# SCH_Linefollowerv1_2022-10-20_plan_A.net
KiCad netlist of a schematic drawn in EasyEDA
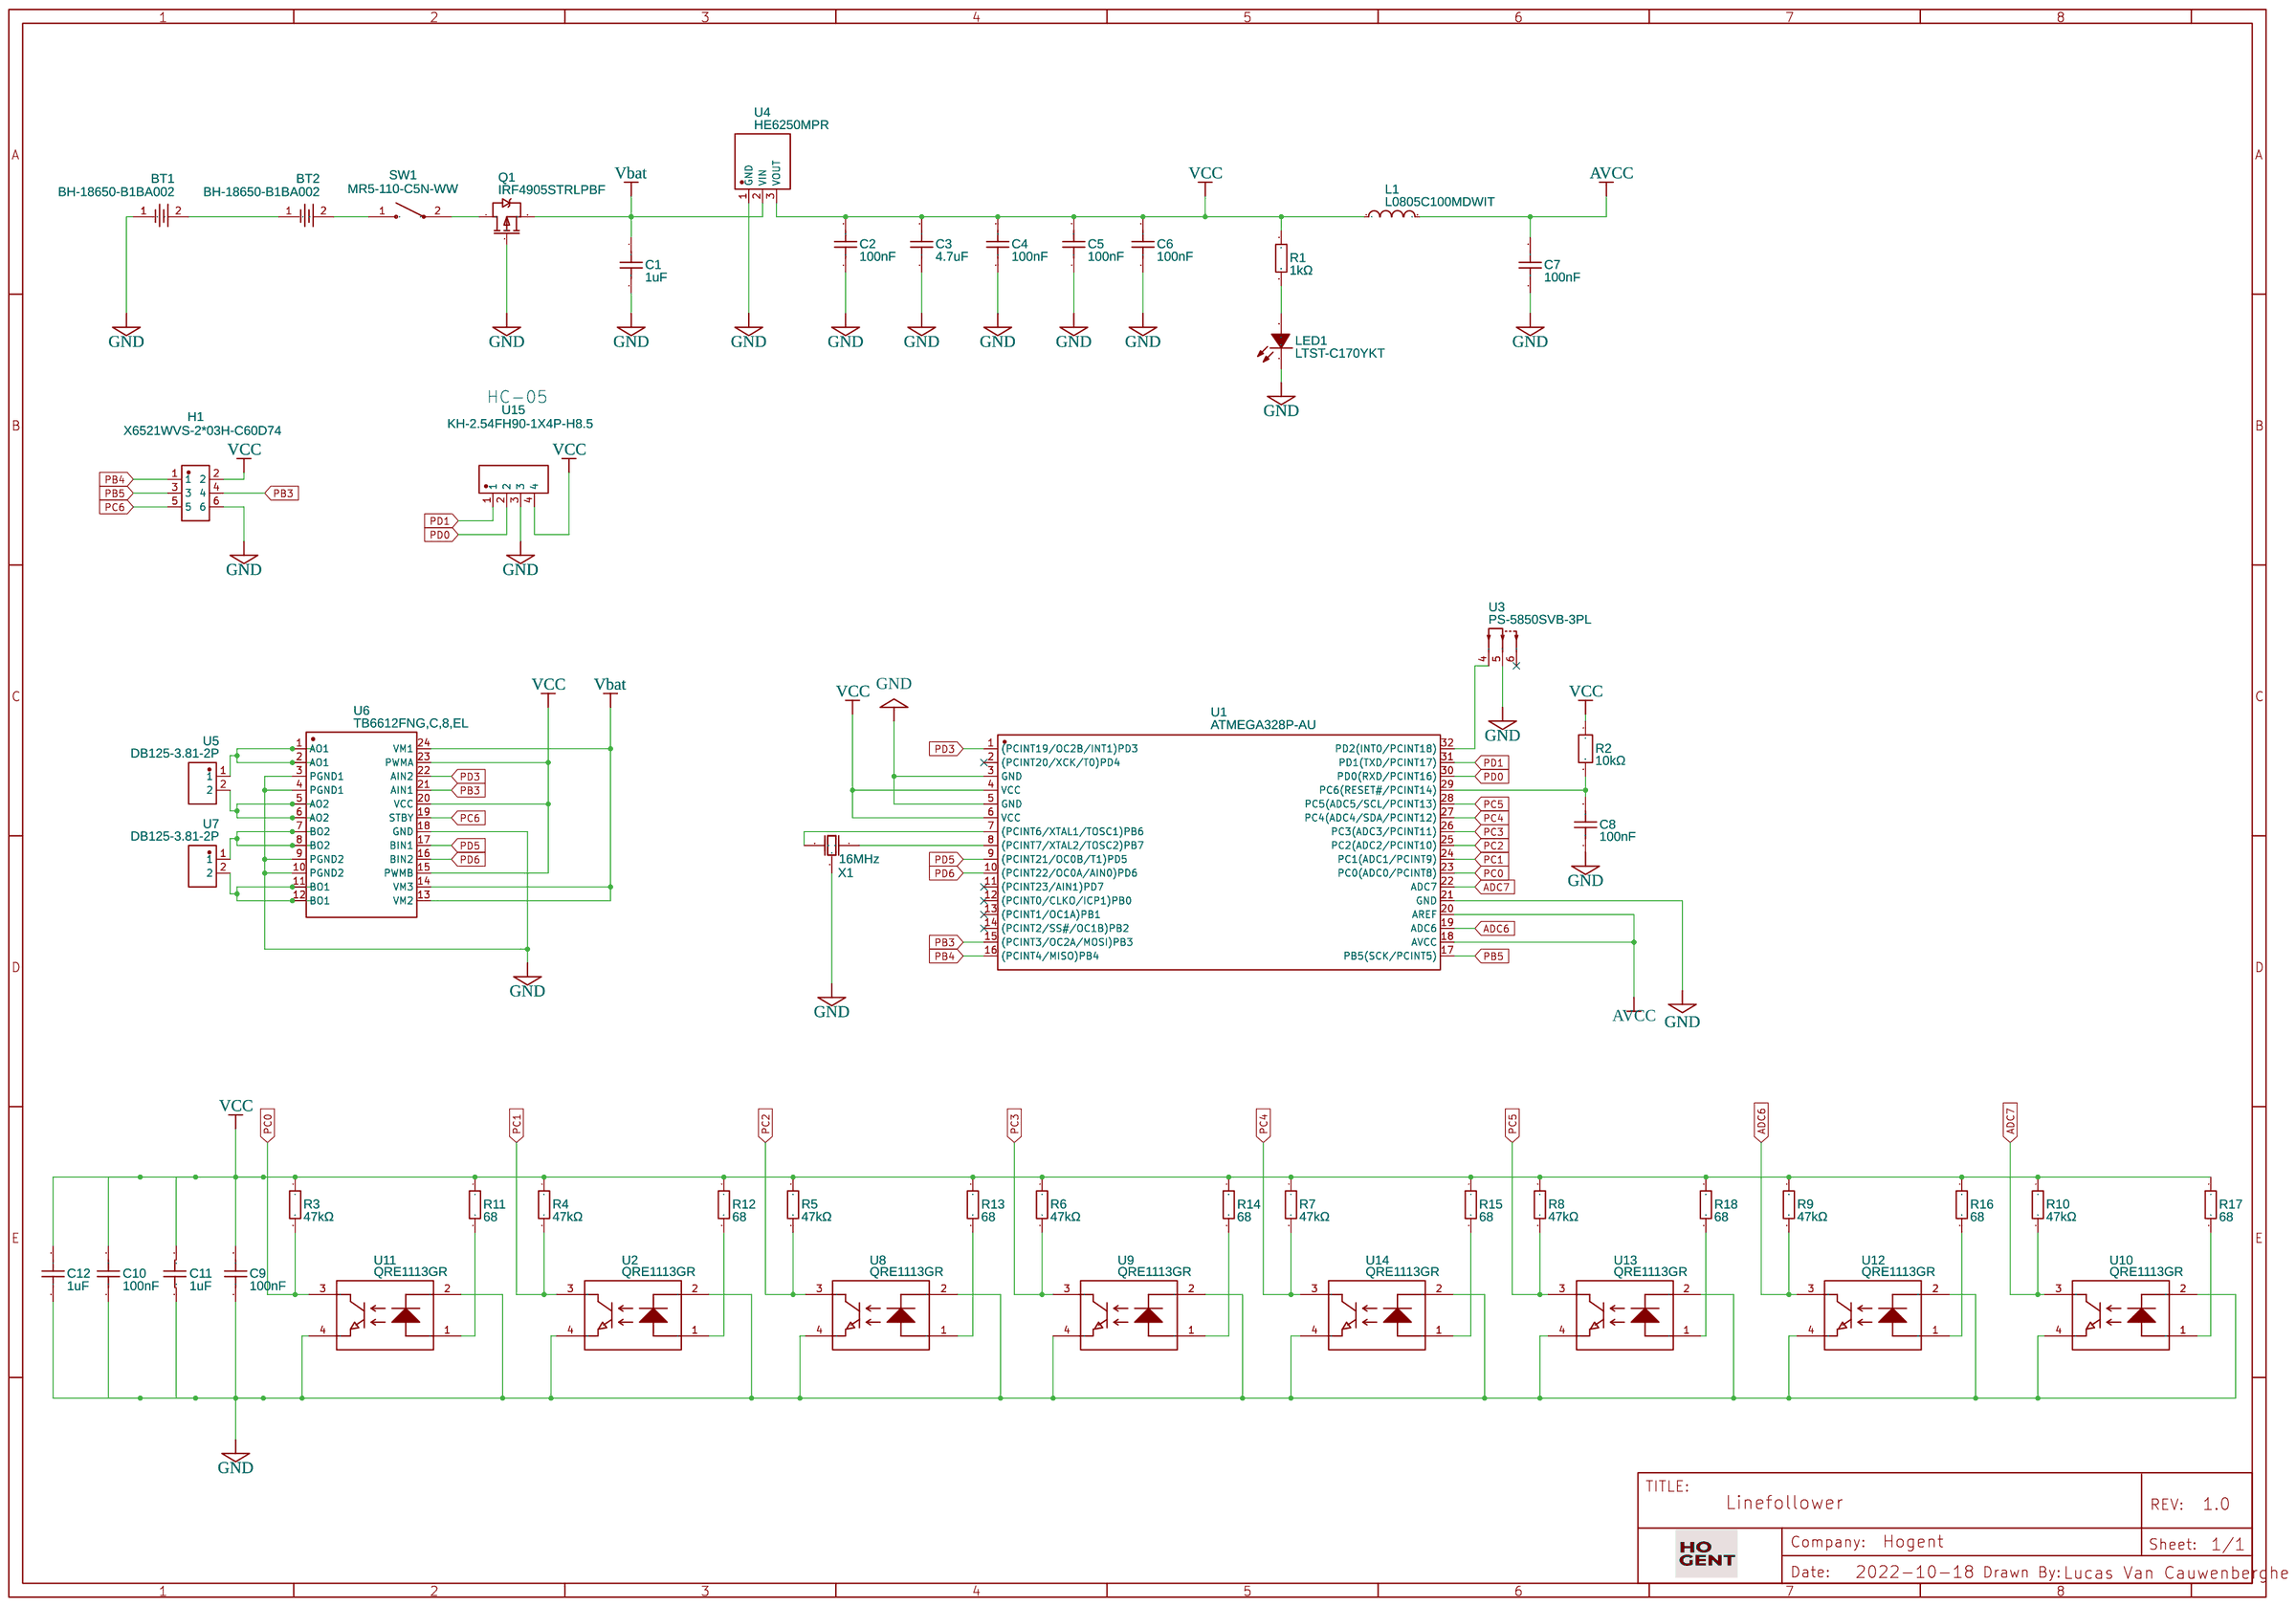
[diagram p0: schematic sheet]

(export (version "E")
  (design (tool "Eeschema 10.0.6"))
  (components
    (comp (ref "BT1")
      (value "BH-18650-B1BA002")
      (fields (field (name "BOM_Supplier Part") "C2988620"))
      (libsource (lib "") (part "BH-18650-B1BA002"))
    )
    (comp (ref "BT2")
      (value "BH-18650-B1BA002")
      (fields (field (name "BOM_Supplier Part") "C2988620"))
      (libsource (lib "") (part "BH-18650-B1BA002"))
    )
    (comp (ref "C1")
      (value "1uF")
      (fields
        (field (name "BOM_Manufacturer Part") "LMK212BJ105KD-T")
        (field (name "BOM_Supplier Part") "C92812")
      )
      (libsource (lib "") (part "LMK212BJ105KD-T"))
    )
    (comp (ref "C2")
      (value "100nF")
      (fields
        (field (name "BOM_Manufacturer Part") "LMK212SD104KG-T")
        (field (name "BOM_Supplier Part") "C386062")
      )
      (libsource (lib "") (part "LMK212SD104KG-T"))
    )
    (comp (ref "C3")
      (value "4.7uF")
      (fields
        (field (name "BOM_Manufacturer Part") "GCM21BC71A475KA73L")
        (field (name "BOM_Supplier Part") "C126583")
      )
      (libsource (lib "") (part "GCM21BC71A475KA73L"))
    )
    (comp (ref "C4")
      (value "100nF")
      (fields
        (field (name "BOM_Manufacturer Part") "LMK212SD104KG-T")
        (field (name "BOM_Supplier Part") "C386062")
      )
      (libsource (lib "") (part "LMK212SD104KG-T"))
    )
    (comp (ref "C5")
      (value "100nF")
      (fields
        (field (name "BOM_Manufacturer Part") "LMK212SD104KG-T")
        (field (name "BOM_Supplier Part") "C386062")
      )
      (libsource (lib "") (part "LMK212SD104KG-T"))
    )
    (comp (ref "C6")
      (value "100nF")
      (fields
        (field (name "BOM_Manufacturer Part") "LMK212SD104KG-T")
        (field (name "BOM_Supplier Part") "C386062")
      )
      (libsource (lib "") (part "LMK212SD104KG-T"))
    )
    (comp (ref "C7")
      (value "100nF")
      (fields
        (field (name "BOM_Manufacturer Part") "LMK212SD104KG-T")
        (field (name "BOM_Supplier Part") "C386062")
      )
      (libsource (lib "") (part "LMK212SD104KG-T"))
    )
    (comp (ref "C8")
      (value "100nF")
      (fields
        (field (name "BOM_Manufacturer Part") "LMK212SD104KG-T")
        (field (name "BOM_Supplier Part") "C386062")
      )
      (libsource (lib "") (part "LMK212SD104KG-T"))
    )
    (comp (ref "C9")
      (value "100nF")
      (fields
        (field (name "BOM_Manufacturer Part") "LMK212SD104KG-T")
        (field (name "BOM_Supplier Part") "C386062")
      )
      (libsource (lib "") (part "LMK212SD104KG-T"))
    )
    (comp (ref "C10")
      (value "100nF")
      (fields
        (field (name "BOM_Manufacturer Part") "LMK212SD104KG-T")
        (field (name "BOM_Supplier Part") "C386062")
      )
      (libsource (lib "") (part "LMK212SD104KG-T"))
    )
    (comp (ref "C11")
      (value "1uF")
      (fields
        (field (name "BOM_Manufacturer Part") "LMK212BJ105KD-T")
        (field (name "BOM_Supplier Part") "C92812")
      )
      (libsource (lib "") (part "LMK212BJ105KD-T_1"))
    )
    (comp (ref "C12")
      (value "1uF")
      (fields
        (field (name "BOM_Manufacturer Part") "LMK212BJ105KD-T")
        (field (name "BOM_Supplier Part") "C92812")
      )
      (libsource (lib "") (part "LMK212BJ105KD-T"))
    )
    (comp (ref "H1")
      (value "X6521WVS-2*03H-C60D74")
      (fields (field (name "BOM_Supplier Part") "C780054"))
      (libsource (lib "") (part "X6521WVS-2*03H-C60D74"))
    )
    (comp (ref "L1")
      (value "L0805C100MDWIT")
      (fields (field (name "BOM_Supplier Part") "C696787"))
      (libsource (lib "") (part "L0805C100MDWIT"))
    )
    (comp (ref "LED1")
      (value "LTST-C170YKT")
      (fields (field (name "BOM_Supplier Part") "C125092"))
      (libsource (lib "") (part "LTST-C170YKT"))
    )
    (comp (ref "Q1")
      (value "IRF4905STRLPBF")
      (fields (field (name "BOM_Supplier Part") "C2620"))
      (libsource (lib "") (part "IRF4905STRLPBF"))
    )
    (comp (ref "R1")
      (value "1kΩ")
      (fields
        (field (name "BOM_Manufacturer Part") "ARG05BTC1001")
        (field (name "BOM_Supplier Part") "C309081")
      )
      (libsource (lib "") (part "ARG05BTC1001"))
    )
    (comp (ref "R2")
      (value "10kΩ")
      (fields
        (field (name "BOM_Manufacturer Part") "ARG05BTC1002")
        (field (name "BOM_Supplier Part") "C406725")
      )
      (libsource (lib "") (part "ARG05BTC1002"))
    )
    (comp (ref "R3")
      (value "47kΩ")
      (fields
        (field (name "BOM_Manufacturer Part") "AECR0805F47K0K9")
        (field (name "BOM_Supplier Part") "C328397")
      )
      (libsource (lib "") (part "AECR0805F47K0K9"))
    )
    (comp (ref "R4")
      (value "47kΩ")
      (fields
        (field (name "BOM_Manufacturer Part") "AECR0805F47K0K9")
        (field (name "BOM_Supplier Part") "C328397")
      )
      (libsource (lib "") (part "AECR0805F47K0K9"))
    )
    (comp (ref "R5")
      (value "47kΩ")
      (fields
        (field (name "BOM_Manufacturer Part") "AECR0805F47K0K9")
        (field (name "BOM_Supplier Part") "C328397")
      )
      (libsource (lib "") (part "AECR0805F47K0K9"))
    )
    (comp (ref "R6")
      (value "47kΩ")
      (fields
        (field (name "BOM_Manufacturer Part") "AECR0805F47K0K9")
        (field (name "BOM_Supplier Part") "C328397")
      )
      (libsource (lib "") (part "AECR0805F47K0K9"))
    )
    (comp (ref "R7")
      (value "47kΩ")
      (fields
        (field (name "BOM_Manufacturer Part") "AECR0805F47K0K9")
        (field (name "BOM_Supplier Part") "C328397")
      )
      (libsource (lib "") (part "AECR0805F47K0K9"))
    )
    (comp (ref "R8")
      (value "47kΩ")
      (fields
        (field (name "BOM_Manufacturer Part") "AECR0805F47K0K9")
        (field (name "BOM_Supplier Part") "C328397")
      )
      (libsource (lib "") (part "AECR0805F47K0K9"))
    )
    (comp (ref "R9")
      (value "47kΩ")
      (fields
        (field (name "BOM_Manufacturer Part") "AECR0805F47K0K9")
        (field (name "BOM_Supplier Part") "C328397")
      )
      (libsource (lib "") (part "AECR0805F47K0K9"))
    )
    (comp (ref "R10")
      (value "47kΩ")
      (fields
        (field (name "BOM_Manufacturer Part") "AECR0805F47K0K9")
        (field (name "BOM_Supplier Part") "C328397")
      )
      (libsource (lib "") (part "AECR0805F47K0K9"))
    )
    (comp (ref "R11")
      (value "68")
      (fields
        (field (name "BOM_Manufacturer Part") "RC0805FR-0768RL")
        (field (name "BOM_Supplier Part") "C137498")
      )
      (libsource (lib "") (part "RC0805FR-0768RL"))
    )
    (comp (ref "R12")
      (value "68")
      (fields
        (field (name "BOM_Manufacturer Part") "RC0805FR-0768RL")
        (field (name "BOM_Supplier Part") "C137498")
      )
      (libsource (lib "") (part "RC0805FR-0768RL"))
    )
    (comp (ref "R13")
      (value "68")
      (fields
        (field (name "BOM_Manufacturer Part") "RC0805FR-0768RL")
        (field (name "BOM_Supplier Part") "C137498")
      )
      (libsource (lib "") (part "RC0805FR-0768RL"))
    )
    (comp (ref "R14")
      (value "68")
      (fields
        (field (name "BOM_Manufacturer Part") "RC0805FR-0768RL")
        (field (name "BOM_Supplier Part") "C137498")
      )
      (libsource (lib "") (part "RC0805FR-0768RL"))
    )
    (comp (ref "R15")
      (value "68")
      (fields
        (field (name "BOM_Manufacturer Part") "RC0805FR-0768RL")
        (field (name "BOM_Supplier Part") "C137498")
      )
      (libsource (lib "") (part "RC0805FR-0768RL"))
    )
    (comp (ref "R16")
      (value "68")
      (fields
        (field (name "BOM_Manufacturer Part") "RC0805FR-0768RL")
        (field (name "BOM_Supplier Part") "C137498")
      )
      (libsource (lib "") (part "RC0805FR-0768RL"))
    )
    (comp (ref "R17")
      (value "68")
      (fields
        (field (name "BOM_Manufacturer Part") "RC0805FR-0768RL")
        (field (name "BOM_Supplier Part") "C137498")
      )
      (libsource (lib "") (part "RC0805FR-0768RL"))
    )
    (comp (ref "R18")
      (value "68")
      (fields
        (field (name "BOM_Manufacturer Part") "RC0805FR-0768RL")
        (field (name "BOM_Supplier Part") "C137498")
      )
      (libsource (lib "") (part "RC0805FR-0768RL"))
    )
    (comp (ref "SW1")
      (value "MR5-110-C5N-WW")
      (fields (field (name "BOM_Supplier Part") "C2829507"))
      (libsource (lib "") (part "MR5-110-C5N-WW"))
    )
    (comp (ref "U1")
      (value "ATMEGA328P-AU")
      (fields (field (name "BOM_Supplier Part") "C14877"))
      (libsource (lib "") (part "ATMEGA328P-AU"))
    )
    (comp (ref "U2")
      (value "QRE1113GR")
      (fields (field (name "BOM_Supplier Part") "C232862"))
      (libsource (lib "") (part "QRE1113GR_5"))
    )
    (comp (ref "U3")
      (value "PS-5850SVB-3PL")
      (fields (field (name "BOM_Supplier Part") "C5159077"))
      (libsource (lib "") (part "PS-5850SVB-3PL"))
    )
    (comp (ref "U4")
      (value "HE6250MPR")
      (fields (field (name "BOM_Supplier Part") "C711940"))
      (libsource (lib "") (part "HE6250MPR"))
    )
    (comp (ref "U5")
      (value "DB125-3.81-2P")
      (fields (field (name "BOM_Supplier Part") "C395878"))
      (libsource (lib "") (part "DB125-3.81-2P"))
    )
    (comp (ref "U6")
      (value "TB6612FNG,C,8,EL")
      (fields (field (name "BOM_Supplier Part") "C141517"))
      (libsource (lib "") (part "Unknown_500_-570"))
    )
    (comp (ref "U7")
      (value "DB125-3.81-2P")
      (fields (field (name "BOM_Supplier Part") "C395878"))
      (libsource (lib "") (part "DB125-3.81-2P"))
    )
    (comp (ref "U8")
      (value "QRE1113GR")
      (fields (field (name "BOM_Supplier Part") "C232862"))
      (libsource (lib "") (part "QRE1113GR_4"))
    )
    (comp (ref "U9")
      (value "QRE1113GR")
      (fields (field (name "BOM_Supplier Part") "C232862"))
      (libsource (lib "") (part "QRE1113GR_6"))
    )
    (comp (ref "U10")
      (value "QRE1113GR")
      (fields (field (name "BOM_Supplier Part") "C232862"))
      (libsource (lib "") (part "QRE1113GR_2"))
    )
    (comp (ref "U11")
      (value "QRE1113GR")
      (fields (field (name "BOM_Supplier Part") "C232862"))
      (libsource (lib "") (part "QRE1113GR_2"))
    )
    (comp (ref "U12")
      (value "QRE1113GR")
      (fields (field (name "BOM_Supplier Part") "C232862"))
      (libsource (lib "") (part "QRE1113GR"))
    )
    (comp (ref "U13")
      (value "QRE1113GR")
      (fields (field (name "BOM_Supplier Part") "C232862"))
      (libsource (lib "") (part "QRE1113GR_3"))
    )
    (comp (ref "U14")
      (value "QRE1113GR")
      (fields (field (name "BOM_Supplier Part") "C232862"))
      (libsource (lib "") (part "QRE1113GR_1"))
    )
    (comp (ref "U15")
      (value "KH-2.54FH90-1X4P-H8.5")
      (fields (field (name "BOM_Supplier Part") "C2932680"))
      (libsource (lib "") (part "KH-2.54FH90-1X4P-H8.5"))
    )
    (comp (ref "X1")
      (value "16MHz")
      (fields
        (field (name "BOM_Manufacturer Part") "CSTNE16M0V53C000R0")
        (field (name "BOM_Supplier Part") "C882606")
      )
      (libsource (lib "") (part "CSTNE16M0V53C000R0"))
    )
  )
  (nets
    (net (code "1") (name "ADC6") (class "Default")
      (node (ref "R9") (pin "2") (pinfunction "2_2") (pintype "unspecified"))
      (node (ref "U1") (pin "19") (pinfunction "ADC6_19") (pintype "unspecified"))
      (node (ref "U12") (pin "3") (pinfunction "3_3") (pintype "input"))
    )
    (net (code "2") (name "ADC7") (class "Default")
      (node (ref "R10") (pin "2") (pinfunction "2_2") (pintype "unspecified"))
      (node (ref "U1") (pin "22") (pinfunction "ADC7_22") (pintype "unspecified"))
      (node (ref "U10") (pin "3") (pinfunction "3_3") (pintype "input"))
    )
    (net (code "3") (name "AVCC") (class "Default")
      (node (ref "C7") (pin "2") (pinfunction "2_2") (pintype "unspecified"))
      (node (ref "L1") (pin "2") (pinfunction "2_2") (pintype "unspecified"))
      (node (ref "U1") (pin "18") (pinfunction "AVCC_18") (pintype "unspecified"))
      (node (ref "U1") (pin "20") (pinfunction "AREF_20") (pintype "unspecified"))
    )
    (net (code "4") (name "GND") (class "Default")
      (node (ref "BT1") (pin "1") (pinfunction "1_1") (pintype "input"))
      (node (ref "C1") (pin "2") (pinfunction "2_2") (pintype "unspecified"))
      (node (ref "C10") (pin "1") (pinfunction "1_1") (pintype "unspecified"))
      (node (ref "C11") (pin "2") (pinfunction "2_2") (pintype "unspecified"))
      (node (ref "C12") (pin "2") (pinfunction "2_2") (pintype "unspecified"))
      (node (ref "C2") (pin "1") (pinfunction "1_1") (pintype "unspecified"))
      (node (ref "C3") (pin "1") (pinfunction "1_1") (pintype "unspecified"))
      (node (ref "C4") (pin "1") (pinfunction "1_1") (pintype "unspecified"))
      (node (ref "C5") (pin "1") (pinfunction "1_1") (pintype "unspecified"))
      (node (ref "C6") (pin "1") (pinfunction "1_1") (pintype "unspecified"))
      (node (ref "C7") (pin "1") (pinfunction "1_1") (pintype "unspecified"))
      (node (ref "C8") (pin "1") (pinfunction "1_1") (pintype "unspecified"))
      (node (ref "C9") (pin "1") (pinfunction "1_1") (pintype "unspecified"))
      (node (ref "H1") (pin "6") (pinfunction "6_6") (pintype "unspecified"))
      (node (ref "LED1") (pin "1") (pinfunction "1_1") (pintype "unspecified"))
      (node (ref "Q1") (pin "1") (pinfunction "G_1") (pintype "unspecified"))
      (node (ref "U1") (pin "21") (pinfunction "GND_21") (pintype "unspecified"))
      (node (ref "U1") (pin "3") (pinfunction "GND_3") (pintype "unspecified"))
      (node (ref "U1") (pin "5") (pinfunction "GND_5") (pintype "unspecified"))
      (node (ref "U10") (pin "2") (pinfunction "2_2") (pintype "input"))
      (node (ref "U10") (pin "4") (pinfunction "4_4") (pintype "input"))
      (node (ref "U11") (pin "2") (pinfunction "2_2") (pintype "input"))
      (node (ref "U11") (pin "4") (pinfunction "4_4") (pintype "input"))
      (node (ref "U12") (pin "2") (pinfunction "2_2") (pintype "input"))
      (node (ref "U12") (pin "4") (pinfunction "4_4") (pintype "input"))
      (node (ref "U13") (pin "2") (pinfunction "2_2") (pintype "input"))
      (node (ref "U13") (pin "4") (pinfunction "4_4") (pintype "input"))
      (node (ref "U14") (pin "2") (pinfunction "2_2") (pintype "input"))
      (node (ref "U14") (pin "4") (pinfunction "4_4") (pintype "input"))
      (node (ref "U15") (pin "3") (pinfunction "3_3") (pintype "unspecified"))
      (node (ref "U2") (pin "2") (pinfunction "2_2") (pintype "input"))
      (node (ref "U2") (pin "4") (pinfunction "4_4") (pintype "input"))
      (node (ref "U3") (pin "5") (pinfunction "5_5") (pintype "unspecified"))
      (node (ref "U4") (pin "1") (pinfunction "GND_1") (pintype "unspecified"))
      (node (ref "U6") (pin "10") (pinfunction "PGND2_10") (pintype "unspecified"))
      (node (ref "U6") (pin "18") (pinfunction "GND_18") (pintype "unspecified"))
      (node (ref "U6") (pin "3") (pinfunction "PGND1_3") (pintype "unspecified"))
      (node (ref "U6") (pin "4") (pinfunction "PGND1_4") (pintype "unspecified"))
      (node (ref "U6") (pin "9") (pinfunction "PGND2_9") (pintype "unspecified"))
      (node (ref "U8") (pin "2") (pinfunction "2_2") (pintype "input"))
      (node (ref "U8") (pin "4") (pinfunction "4_4") (pintype "input"))
      (node (ref "U9") (pin "2") (pinfunction "2_2") (pintype "input"))
      (node (ref "U9") (pin "4") (pinfunction "4_4") (pintype "input"))
      (node (ref "X1") (pin "2") (pinfunction "GND_2") (pintype "input"))
    )
    (net (code "5") (name "Net-(BT1-Pad2)") (class "Default")
      (node (ref "BT1") (pin "2") (pinfunction "2_2") (pintype "input"))
      (node (ref "BT2") (pin "1") (pinfunction "1_1") (pintype "input"))
    )
    (net (code "6") (name "Net-(BT2-Pad2)") (class "Default")
      (node (ref "BT2") (pin "2") (pinfunction "2_2") (pintype "input"))
      (node (ref "SW1") (pin "1") (pinfunction "1_1") (pintype "unspecified"))
    )
    (net (code "7") (name "Net-(LED1-Pad2)") (class "Default")
      (node (ref "LED1") (pin "2") (pinfunction "2_2") (pintype "unspecified"))
      (node (ref "R1") (pin "2") (pinfunction "2_2") (pintype "unspecified"))
    )
    (net (code "8") (name "Net-(Q1-D)") (class "Default")
      (node (ref "Q1") (pin "4") (pinfunction "D_4") (pintype "unspecified"))
      (node (ref "SW1") (pin "2") (pinfunction "2_2") (pintype "unspecified"))
    )
    (net (code "9") (name "Net-(R11-Pad2)") (class "Default")
      (node (ref "R11") (pin "2") (pinfunction "2_2") (pintype "input"))
      (node (ref "U11") (pin "1") (pinfunction "1_1") (pintype "input"))
    )
    (net (code "10") (name "Net-(R12-Pad2)") (class "Default")
      (node (ref "R12") (pin "2") (pinfunction "2_2") (pintype "input"))
      (node (ref "U2") (pin "1") (pinfunction "1_1") (pintype "input"))
    )
    (net (code "11") (name "Net-(R13-Pad2)") (class "Default")
      (node (ref "R13") (pin "2") (pinfunction "2_2") (pintype "input"))
      (node (ref "U8") (pin "1") (pinfunction "1_1") (pintype "input"))
    )
    (net (code "12") (name "Net-(R14-Pad2)") (class "Default")
      (node (ref "R14") (pin "2") (pinfunction "2_2") (pintype "input"))
      (node (ref "U9") (pin "1") (pinfunction "1_1") (pintype "input"))
    )
    (net (code "13") (name "Net-(R15-Pad2)") (class "Default")
      (node (ref "R15") (pin "2") (pinfunction "2_2") (pintype "input"))
      (node (ref "U14") (pin "1") (pinfunction "1_1") (pintype "input"))
    )
    (net (code "14") (name "Net-(R16-Pad2)") (class "Default")
      (node (ref "R16") (pin "2") (pinfunction "2_2") (pintype "input"))
      (node (ref "U12") (pin "1") (pinfunction "1_1") (pintype "input"))
    )
    (net (code "15") (name "Net-(R17-Pad2)") (class "Default")
      (node (ref "R17") (pin "2") (pinfunction "2_2") (pintype "input"))
      (node (ref "U10") (pin "1") (pinfunction "1_1") (pintype "input"))
    )
    (net (code "16") (name "Net-(R18-Pad2)") (class "Default")
      (node (ref "R18") (pin "2") (pinfunction "2_2") (pintype "input"))
      (node (ref "U13") (pin "1") (pinfunction "1_1") (pintype "input"))
    )
    (net (code "17") (name "Net-(U1-(PCINT6{slash}XTAL1{slash}TOSC1)PB6)") (class "Default")
      (node (ref "U1") (pin "7") (pinfunction "(PCINT6/XTAL1/TOSC1)PB6_7") (pintype "unspecified"))
      (node (ref "X1") (pin "3") (pinfunction "OSC2_3") (pintype "input"))
    )
    (net (code "18") (name "Net-(U1-(PCINT7{slash}XTAL2{slash}TOSC2)PB7)") (class "Default")
      (node (ref "U1") (pin "8") (pinfunction "(PCINT7/XTAL2/TOSC2)PB7_8") (pintype "unspecified"))
      (node (ref "X1") (pin "1") (pinfunction "OSC1_1") (pintype "input"))
    )
    (net (code "19") (name "Net-(U1-PC6(RESET#{slash}PCINT14))") (class "Default")
      (node (ref "C8") (pin "2") (pinfunction "2_2") (pintype "unspecified"))
      (node (ref "R2") (pin "2") (pinfunction "2_2") (pintype "unspecified"))
      (node (ref "U1") (pin "29") (pinfunction "PC6(RESET#/PCINT14)_29") (pintype "unspecified"))
    )
    (net (code "20") (name "Net-(U1-PD2(INT0{slash}PCINT18))") (class "Default")
      (node (ref "U1") (pin "32") (pinfunction "PD2(INT0/PCINT18)_32") (pintype "unspecified"))
      (node (ref "U3") (pin "4") (pinfunction "4_4") (pintype "unspecified"))
    )
    (net (code "21") (name "Net-(U5-Pad1)") (class "Default")
      (node (ref "U5") (pin "1") (pinfunction "1_1") (pintype "unspecified"))
      (node (ref "U6") (pin "1") (pinfunction "AO1_1") (pintype "unspecified"))
      (node (ref "U6") (pin "2") (pinfunction "AO1_2") (pintype "unspecified"))
    )
    (net (code "22") (name "Net-(U5-Pad2)") (class "Default")
      (node (ref "U5") (pin "2") (pinfunction "2_2") (pintype "unspecified"))
      (node (ref "U6") (pin "5") (pinfunction "AO2_5") (pintype "unspecified"))
      (node (ref "U6") (pin "6") (pinfunction "AO2_6") (pintype "unspecified"))
    )
    (net (code "23") (name "Net-(U6-BO1-Pad11)") (class "Default")
      (node (ref "U6") (pin "11") (pinfunction "BO1_11") (pintype "unspecified"))
      (node (ref "U6") (pin "12") (pinfunction "BO1_12") (pintype "unspecified"))
      (node (ref "U7") (pin "2") (pinfunction "2_2") (pintype "unspecified"))
    )
    (net (code "24") (name "Net-(U6-BO2-Pad7)") (class "Default")
      (node (ref "U6") (pin "7") (pinfunction "BO2_7") (pintype "unspecified"))
      (node (ref "U6") (pin "8") (pinfunction "BO2_8") (pintype "unspecified"))
      (node (ref "U7") (pin "1") (pinfunction "1_1") (pintype "unspecified"))
    )
    (net (code "25") (name "PB3") (class "Default")
      (node (ref "H1") (pin "4") (pinfunction "4_4") (pintype "unspecified"))
      (node (ref "U1") (pin "15") (pinfunction "(PCINT3/OC2A/MOSI)PB3_15") (pintype "unspecified"))
      (node (ref "U6") (pin "21") (pinfunction "AIN1_21") (pintype "unspecified"))
    )
    (net (code "26") (name "PB4") (class "Default")
      (node (ref "H1") (pin "1") (pinfunction "1_1") (pintype "unspecified"))
      (node (ref "U1") (pin "16") (pinfunction "(PCINT4/MISO)PB4_16") (pintype "unspecified"))
    )
    (net (code "27") (name "PB5") (class "Default")
      (node (ref "H1") (pin "3") (pinfunction "3_3") (pintype "unspecified"))
      (node (ref "U1") (pin "17") (pinfunction "PB5(SCK/PCINT5)_17") (pintype "unspecified"))
    )
    (net (code "28") (name "PC0") (class "Default")
      (node (ref "R3") (pin "2") (pinfunction "2_2") (pintype "unspecified"))
      (node (ref "U1") (pin "23") (pinfunction "PC0(ADC0/PCINT8)_23") (pintype "unspecified"))
      (node (ref "U11") (pin "3") (pinfunction "3_3") (pintype "input"))
    )
    (net (code "29") (name "PC1") (class "Default")
      (node (ref "R4") (pin "2") (pinfunction "2_2") (pintype "unspecified"))
      (node (ref "U1") (pin "24") (pinfunction "PC1(ADC1/PCINT9)_24") (pintype "unspecified"))
      (node (ref "U2") (pin "3") (pinfunction "3_3") (pintype "input"))
    )
    (net (code "30") (name "PC2") (class "Default")
      (node (ref "R5") (pin "2") (pinfunction "2_2") (pintype "unspecified"))
      (node (ref "U1") (pin "25") (pinfunction "PC2(ADC2/PCINT10)_25") (pintype "unspecified"))
      (node (ref "U8") (pin "3") (pinfunction "3_3") (pintype "input"))
    )
    (net (code "31") (name "PC3") (class "Default")
      (node (ref "R6") (pin "2") (pinfunction "2_2") (pintype "unspecified"))
      (node (ref "U1") (pin "26") (pinfunction "PC3(ADC3/PCINT11)_26") (pintype "unspecified"))
      (node (ref "U9") (pin "3") (pinfunction "3_3") (pintype "input"))
    )
    (net (code "32") (name "PC4") (class "Default")
      (node (ref "R7") (pin "2") (pinfunction "2_2") (pintype "unspecified"))
      (node (ref "U1") (pin "27") (pinfunction "PC4(ADC4/SDA/PCINT12)_27") (pintype "unspecified"))
      (node (ref "U14") (pin "3") (pinfunction "3_3") (pintype "input"))
    )
    (net (code "33") (name "PC5") (class "Default")
      (node (ref "R8") (pin "2") (pinfunction "2_2") (pintype "unspecified"))
      (node (ref "U1") (pin "28") (pinfunction "PC5(ADC5/SCL/PCINT13)_28") (pintype "unspecified"))
      (node (ref "U13") (pin "3") (pinfunction "3_3") (pintype "input"))
    )
    (net (code "34") (name "PC6") (class "Default")
      (node (ref "H1") (pin "5") (pinfunction "5_5") (pintype "unspecified"))
      (node (ref "U6") (pin "19") (pinfunction "STBY_19") (pintype "unspecified"))
    )
    (net (code "35") (name "PD0") (class "Default")
      (node (ref "U1") (pin "30") (pinfunction "PD0(RXD/PCINT16)_30") (pintype "unspecified"))
      (node (ref "U15") (pin "2") (pinfunction "2_2") (pintype "unspecified"))
    )
    (net (code "36") (name "PD1") (class "Default")
      (node (ref "U1") (pin "31") (pinfunction "PD1(TXD/PCINT17)_31") (pintype "unspecified"))
      (node (ref "U15") (pin "1") (pinfunction "1_1") (pintype "unspecified"))
    )
    (net (code "37") (name "PD3") (class "Default")
      (node (ref "U1") (pin "1") (pinfunction "(PCINT19/OC2B/INT1)PD3_1") (pintype "unspecified"))
      (node (ref "U6") (pin "22") (pinfunction "AIN2_22") (pintype "unspecified"))
    )
    (net (code "38") (name "PD5") (class "Default")
      (node (ref "U1") (pin "9") (pinfunction "(PCINT21/OC0B/T1)PD5_9") (pintype "unspecified"))
      (node (ref "U6") (pin "17") (pinfunction "BIN1_17") (pintype "unspecified"))
    )
    (net (code "39") (name "PD6") (class "Default")
      (node (ref "U1") (pin "10") (pinfunction "(PCINT22/OC0A/AIN0)PD6_10") (pintype "unspecified"))
      (node (ref "U6") (pin "16") (pinfunction "BIN2_16") (pintype "unspecified"))
    )
    (net (code "40") (name "VCC") (class "Default")
      (node (ref "C10") (pin "2") (pinfunction "2_2") (pintype "unspecified"))
      (node (ref "C11") (pin "1") (pinfunction "1_1") (pintype "unspecified"))
      (node (ref "C12") (pin "1") (pinfunction "1_1") (pintype "unspecified"))
      (node (ref "C2") (pin "2") (pinfunction "2_2") (pintype "unspecified"))
      (node (ref "C3") (pin "2") (pinfunction "2_2") (pintype "unspecified"))
      (node (ref "C4") (pin "2") (pinfunction "2_2") (pintype "unspecified"))
      (node (ref "C5") (pin "2") (pinfunction "2_2") (pintype "unspecified"))
      (node (ref "C6") (pin "2") (pinfunction "2_2") (pintype "unspecified"))
      (node (ref "C9") (pin "2") (pinfunction "2_2") (pintype "unspecified"))
      (node (ref "H1") (pin "2") (pinfunction "2_2") (pintype "unspecified"))
      (node (ref "L1") (pin "1") (pinfunction "1_1") (pintype "unspecified"))
      (node (ref "R1") (pin "1") (pinfunction "1_1") (pintype "unspecified"))
      (node (ref "R10") (pin "1") (pinfunction "1_1") (pintype "unspecified"))
      (node (ref "R11") (pin "1") (pinfunction "1_1") (pintype "input"))
      (node (ref "R12") (pin "1") (pinfunction "1_1") (pintype "input"))
      (node (ref "R13") (pin "1") (pinfunction "1_1") (pintype "input"))
      (node (ref "R14") (pin "1") (pinfunction "1_1") (pintype "input"))
      (node (ref "R15") (pin "1") (pinfunction "1_1") (pintype "input"))
      (node (ref "R16") (pin "1") (pinfunction "1_1") (pintype "input"))
      (node (ref "R17") (pin "1") (pinfunction "1_1") (pintype "input"))
      (node (ref "R18") (pin "1") (pinfunction "1_1") (pintype "input"))
      (node (ref "R2") (pin "1") (pinfunction "1_1") (pintype "unspecified"))
      (node (ref "R3") (pin "1") (pinfunction "1_1") (pintype "unspecified"))
      (node (ref "R4") (pin "1") (pinfunction "1_1") (pintype "unspecified"))
      (node (ref "R5") (pin "1") (pinfunction "1_1") (pintype "unspecified"))
      (node (ref "R6") (pin "1") (pinfunction "1_1") (pintype "unspecified"))
      (node (ref "R7") (pin "1") (pinfunction "1_1") (pintype "unspecified"))
      (node (ref "R8") (pin "1") (pinfunction "1_1") (pintype "unspecified"))
      (node (ref "R9") (pin "1") (pinfunction "1_1") (pintype "unspecified"))
      (node (ref "U1") (pin "4") (pinfunction "VCC_4") (pintype "unspecified"))
      (node (ref "U1") (pin "6") (pinfunction "VCC_6") (pintype "unspecified"))
      (node (ref "U15") (pin "4") (pinfunction "4_4") (pintype "unspecified"))
      (node (ref "U4") (pin "3") (pinfunction "VOUT_3") (pintype "unspecified"))
      (node (ref "U6") (pin "15") (pinfunction "PWMB_15") (pintype "unspecified"))
      (node (ref "U6") (pin "20") (pinfunction "VCC_20") (pintype "unspecified"))
      (node (ref "U6") (pin "23") (pinfunction "PWMA_23") (pintype "unspecified"))
    )
    (net (code "41") (name "Vbat") (class "Default")
      (node (ref "C1") (pin "1") (pinfunction "1_1") (pintype "unspecified"))
      (node (ref "Q1") (pin "3") (pinfunction "S_3") (pintype "unspecified"))
      (node (ref "U4") (pin "2") (pinfunction "VIN_2") (pintype "unspecified"))
      (node (ref "U6") (pin "13") (pinfunction "VM2_13") (pintype "unspecified"))
      (node (ref "U6") (pin "14") (pinfunction "VM3_14") (pintype "unspecified"))
      (node (ref "U6") (pin "24") (pinfunction "VM1_24") (pintype "unspecified"))
    )
    (net (code "42") (name "unconnected-(U1-(PCINT0{slash}CLKO{slash}ICP1)PB0-Pad12)") (class "Default")
      (node (ref "U1") (pin "12") (pinfunction "(PCINT0/CLKO/ICP1)PB0_12") (pintype "unspecified+no_connect"))
    )
    (net (code "43") (name "unconnected-(U1-(PCINT1{slash}OC1A)PB1-Pad13)") (class "Default")
      (node (ref "U1") (pin "13") (pinfunction "(PCINT1/OC1A)PB1_13") (pintype "unspecified+no_connect"))
    )
    (net (code "44") (name "unconnected-(U1-(PCINT2{slash}SS#{slash}OC1B)PB2-Pad14)") (class "Default")
      (node (ref "U1") (pin "14") (pinfunction "(PCINT2/SS#/OC1B)PB2_14") (pintype "unspecified+no_connect"))
    )
    (net (code "45") (name "unconnected-(U1-(PCINT20{slash}XCK{slash}T0)PD4-Pad2)") (class "Default")
      (node (ref "U1") (pin "2") (pinfunction "(PCINT20/XCK/T0)PD4_2") (pintype "unspecified+no_connect"))
    )
    (net (code "46") (name "unconnected-(U1-(PCINT23{slash}AIN1)PD7-Pad11)") (class "Default")
      (node (ref "U1") (pin "11") (pinfunction "(PCINT23/AIN1)PD7_11") (pintype "unspecified+no_connect"))
    )
    (net (code "47") (name "unconnected-(U3-Pad6)") (class "Default")
      (node (ref "U3") (pin "6") (pinfunction "6_6") (pintype "unspecified+no_connect"))
    )
  )
)
